# LM_HTR_001.net
KiCad netlist of a schematic drawn in Altium Designer
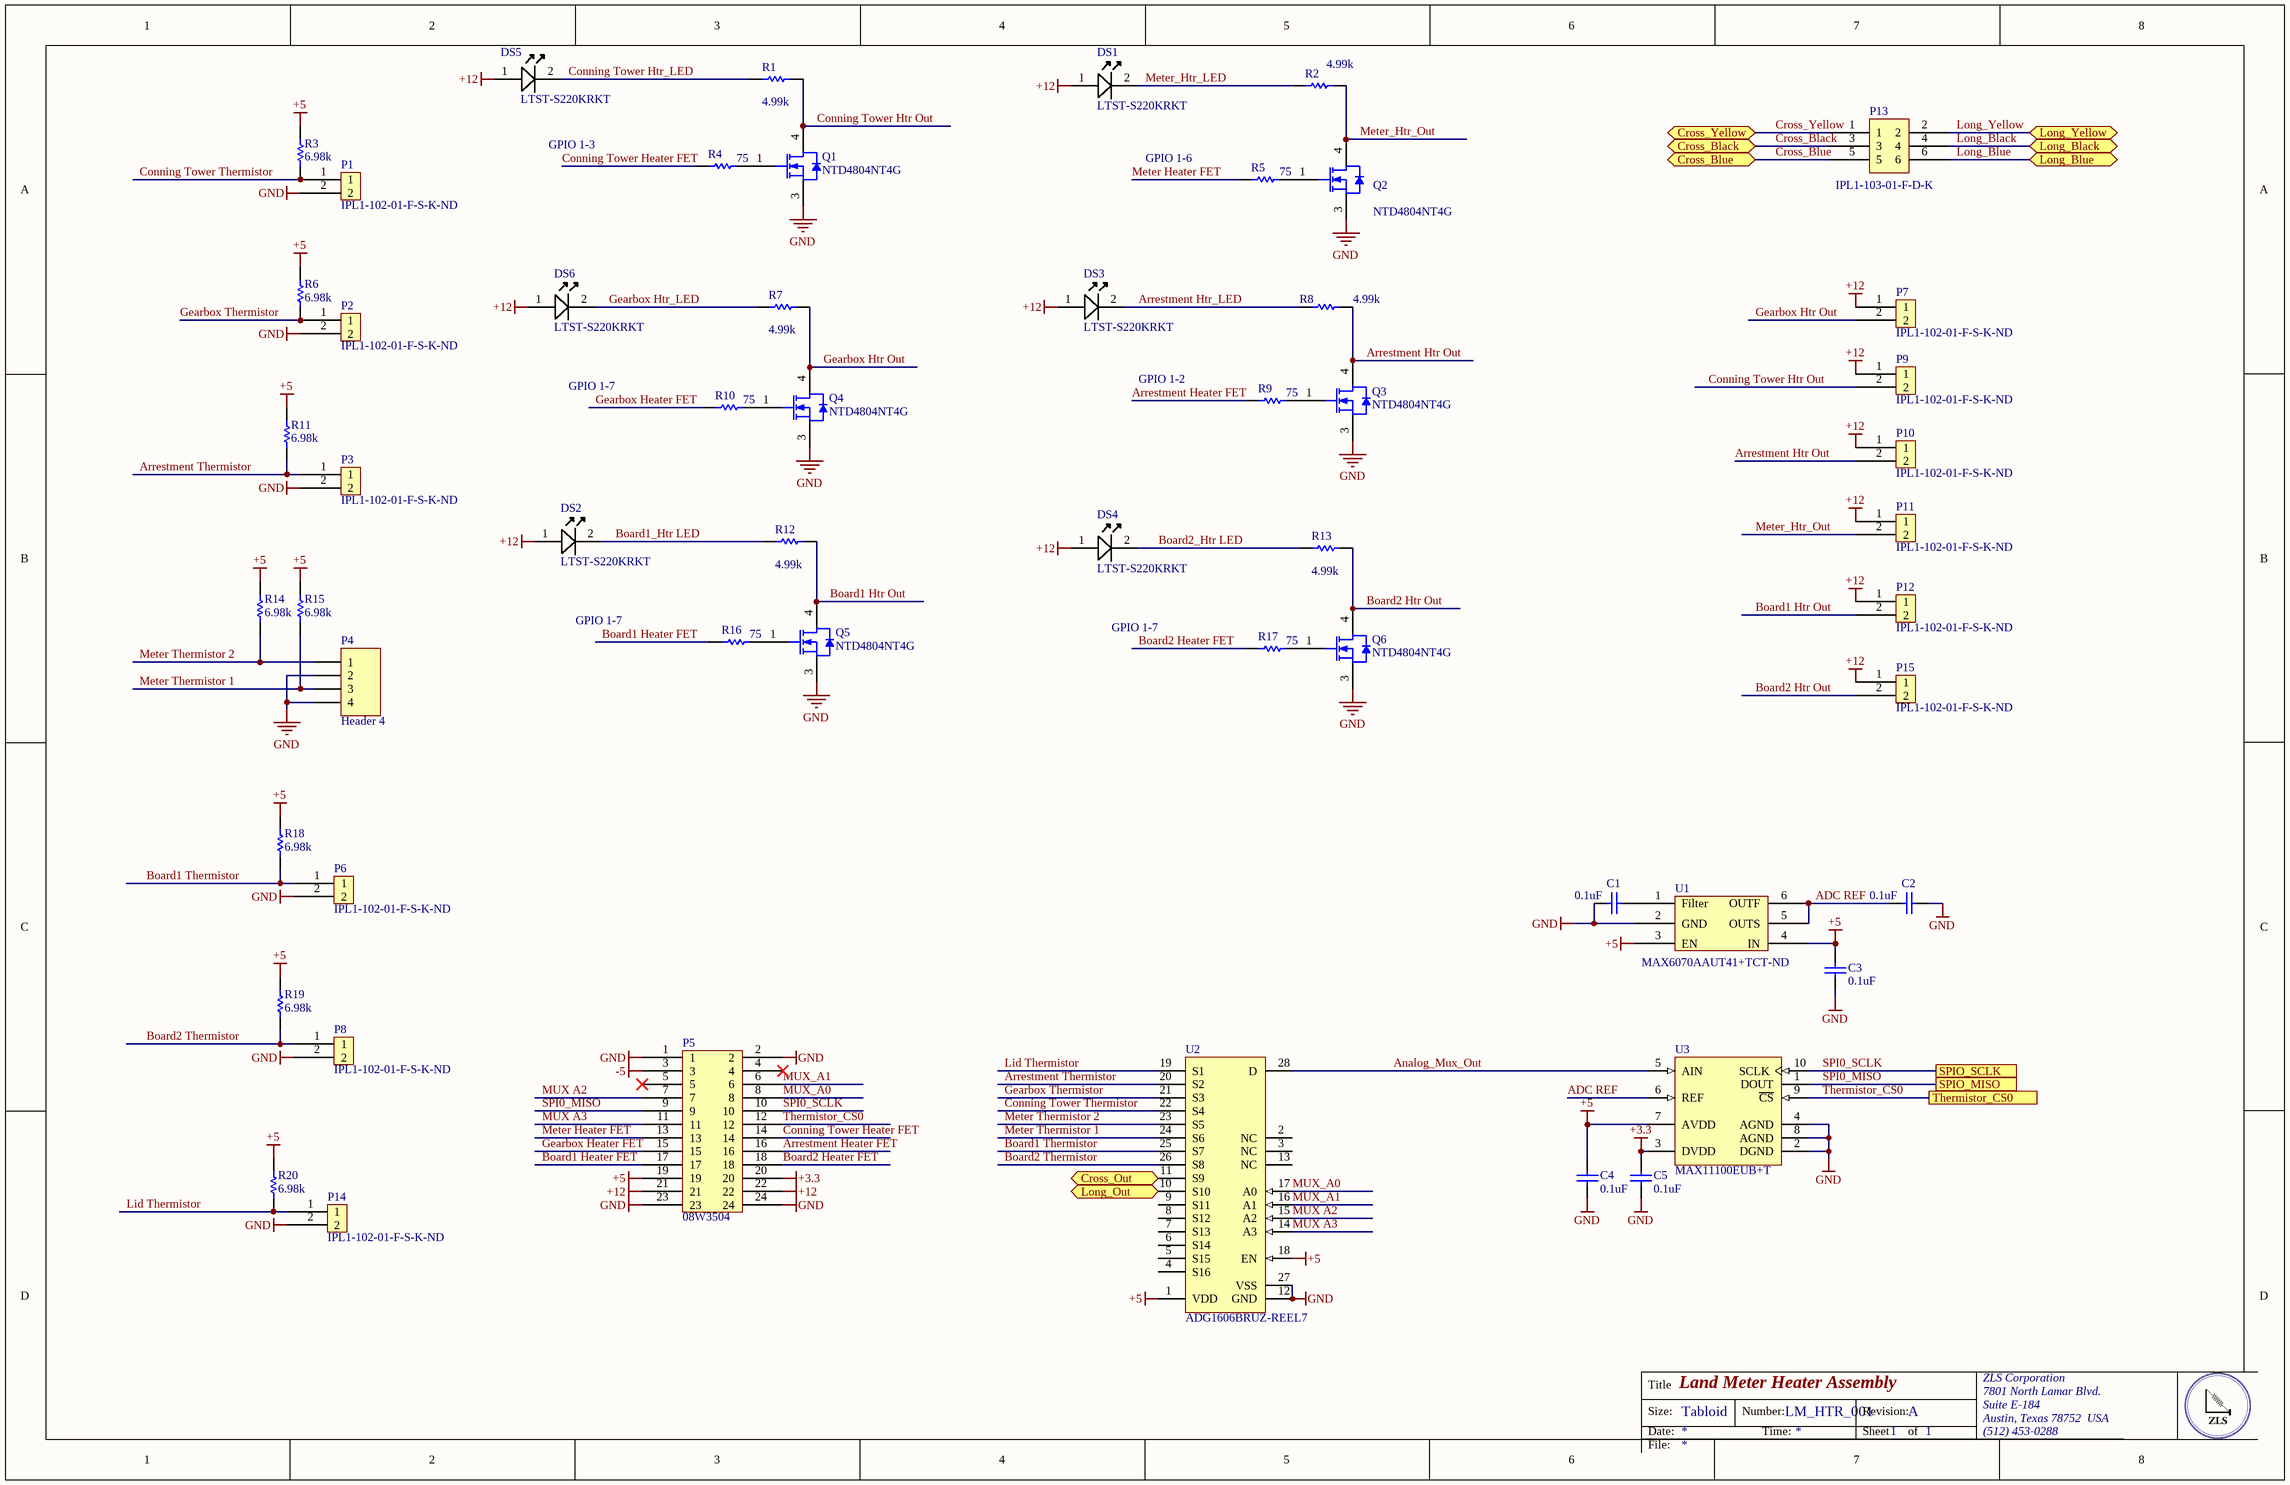
[diagram p0: LM_HTR_001.SchDoc]

(export (version "E")
  (design (tool "Eeschema 10.0.6"))
  (components
    (comp (ref "C1")
      (value "0.1uF")
      (footprint "CAPC0402(1005)60_L")
      (description "CAP CER 0.1UF 10V X7R 0402")
      (fields
        (field (name "MANUFACTURER") "Murata Electronics North America")
        (field (name "MANUFACTURER PART NUMBER") "GRM155R71A104KA01D")
      )
      (libsource (lib "Altium Content Vault") (part "CMP-1034-00252-1"))
    )
    (comp (ref "C2")
      (value "0.1uF")
      (footprint "CAPC0402(1005)60_L")
      (description "CAP CER 0.1UF 10V X7R 0402")
      (fields
        (field (name "MANUFACTURER") "Murata Electronics North America")
        (field (name "MANUFACTURER PART NUMBER") "GRM155R71A104KA01D")
      )
      (libsource (lib "Altium Content Vault") (part "CMP-1034-00252-1"))
    )
    (comp (ref "C3")
      (value "0.1uF")
      (footprint "CAPC0402(1005)60_L")
      (description "CAP CER 0.1UF 10V X7R 0402")
      (fields
        (field (name "MANUFACTURER") "Murata Electronics North America")
        (field (name "MANUFACTURER PART NUMBER") "GRM155R71A104KA01D")
      )
      (libsource (lib "Altium Content Vault") (part "CMP-1034-00252-1"))
    )
    (comp (ref "C4")
      (value "0.1uF")
      (footprint "CAPC0402(1005)60_L")
      (description "CAP CER 0.1UF 10V X7R 0402")
      (fields
        (field (name "MANUFACTURER") "Murata Electronics North America")
        (field (name "MANUFACTURER PART NUMBER") "GRM155R71A104KA01D")
      )
      (libsource (lib "Altium Content Vault") (part "CMP-1034-00252-1"))
    )
    (comp (ref "C5")
      (value "0.1uF")
      (footprint "CAPC0402(1005)60_L")
      (description "CAP CER 0.1UF 10V X7R 0402")
      (fields
        (field (name "MANUFACTURER") "Murata Electronics North America")
        (field (name "MANUFACTURER PART NUMBER") "GRM155R71A104KA01D")
      )
      (libsource (lib "Altium Content Vault") (part "CMP-1034-00252-1"))
    )
    (comp (ref "DS1")
      (value "Visible Name Value Type    False Description Lite-On LTST-S220KRKT Red LED, 631 nm 2012 (0805) Side View, Rectangle Lens SMD package STRING")
      (footprint "0805C_L")
      (fields
        (field (name "MANUFACTURER") "Vishay / Lite-On")
        (field (name "MANUFACTURER PART NUMBER") "LTST-S220KRKT")
      )
      (libsource (lib "*") (part "LED A/K"))
    )
    (comp (ref "DS2")
      (value "Visible Name Value Type    False Description Lite-On LTST-S220KRKT Red LED, 631 nm 2012 (0805) Side View, Rectangle Lens SMD package STRING")
      (footprint "0805C_L")
      (fields
        (field (name "MANUFACTURER") "Vishay / Lite-On")
        (field (name "MANUFACTURER PART NUMBER") "LTST-S220KRKT")
      )
      (libsource (lib "*") (part "LED A/K"))
    )
    (comp (ref "DS3")
      (value "Visible Name Value Type    False Description Lite-On LTST-S220KRKT Red LED, 631 nm 2012 (0805) Side View, Rectangle Lens SMD package STRING")
      (footprint "0805C_L")
      (fields
        (field (name "MANUFACTURER") "Vishay / Lite-On")
        (field (name "MANUFACTURER PART NUMBER") "LTST-S220KRKT")
      )
      (libsource (lib "*") (part "LED A/K"))
    )
    (comp (ref "DS4")
      (value "Visible Name Value Type    False Description Lite-On LTST-S220KRKT Red LED, 631 nm 2012 (0805) Side View, Rectangle Lens SMD package STRING")
      (footprint "0805C_L")
      (fields
        (field (name "MANUFACTURER") "Vishay / Lite-On")
        (field (name "MANUFACTURER PART NUMBER") "LTST-S220KRKT")
      )
      (libsource (lib "*") (part "LED A/K"))
    )
    (comp (ref "DS5")
      (value "Visible Name Value Type    False Description Lite-On LTST-S220KRKT Red LED, 631 nm 2012 (0805) Side View, Rectangle Lens SMD package STRING")
      (footprint "0805C_L")
      (fields
        (field (name "MANUFACTURER") "Vishay / Lite-On")
        (field (name "MANUFACTURER PART NUMBER") "LTST-S220KRKT")
      )
      (libsource (lib "*") (part "LED A/K"))
    )
    (comp (ref "DS6")
      (value "Visible Name Value Type    False Description Lite-On LTST-S220KRKT Red LED, 631 nm 2012 (0805) Side View, Rectangle Lens SMD package STRING")
      (footprint "0805C_L")
      (fields
        (field (name "MANUFACTURER") "Vishay / Lite-On")
        (field (name "MANUFACTURER PART NUMBER") "LTST-S220KRKT")
      )
      (libsource (lib "*") (part "LED A/K"))
    )
    (comp (ref "P1")
      (value "IPL1-102-01-F-S-K")
      (footprint "IPL1-102-01-F-S-K")
      (description ".100 TERMINAL ASSEMBLY")
      (fields
        (field (name "SUPPLIER PART NUMBER 1") "IPL1-102-01-F-S-K-ND")
        (field (name "MANUFACTURER") "Samtec Inc.")
      )
      (libsource (lib "ZLS_Schematic_lib") (part "IPL1-102-01-F-S-K"))
    )
    (comp (ref "P2")
      (value "IPL1-102-01-F-S-K")
      (footprint "IPL1-102-01-F-S-K")
      (description ".100 TERMINAL ASSEMBLY")
      (fields
        (field (name "SUPPLIER PART NUMBER 1") "IPL1-102-01-F-S-K-ND")
        (field (name "MANUFACTURER") "Samtec Inc.")
      )
      (libsource (lib "ZLS_Schematic_lib") (part "IPL1-102-01-F-S-K"))
    )
    (comp (ref "P3")
      (value "IPL1-102-01-F-S-K")
      (footprint "IPL1-102-01-F-S-K")
      (description ".100 TERMINAL ASSEMBLY")
      (fields
        (field (name "SUPPLIER PART NUMBER 1") "IPL1-102-01-F-S-K-ND")
        (field (name "MANUFACTURER") "Samtec Inc.")
      )
      (libsource (lib "ZLS_Schematic_lib") (part "IPL1-102-01-F-S-K"))
    )
    (comp (ref "P4")
      (value "Header 4")
      (footprint "IPL1-104-01-L-S-K")
      (description "Header, 4-Pin")
      (fields (field (name "PUBLISHER") "Altium Limited"))
      (libsource (lib "Miscellaneous Connectors") (part "Header 4"))
    )
    (comp (ref "P5")
      (value "IPL1-112-01-F-S-K")
      (footprint "IPL1-112-01-F-S-K")
      (description "IPL1-112-01-F-D-K")
      (fields (field (name "SUPPLIER PART NUMBER 1") "08W3504"))
      (libsource (lib "ZLS_Schematic_lib") (part "IPL1-112-01-F-S-K"))
    )
    (comp (ref "P6")
      (value "IPL1-102-01-F-S-K")
      (footprint "IPL1-102-01-F-S-K")
      (description ".100 TERMINAL ASSEMBLY")
      (fields
        (field (name "SUPPLIER PART NUMBER 1") "IPL1-102-01-F-S-K-ND")
        (field (name "MANUFACTURER") "Samtec Inc.")
      )
      (libsource (lib "ZLS_Schematic_lib") (part "IPL1-102-01-F-S-K"))
    )
    (comp (ref "P7")
      (value "IPL1-102-01-F-S-K")
      (footprint "IPL1-102-01-F-S-K")
      (description ".100 TERMINAL ASSEMBLY")
      (fields
        (field (name "SUPPLIER PART NUMBER 1") "IPL1-102-01-F-S-K-ND")
        (field (name "MANUFACTURER") "Samtec Inc.")
      )
      (libsource (lib "ZLS_Schematic_lib") (part "IPL1-102-01-F-S-K"))
    )
    (comp (ref "P8")
      (value "IPL1-102-01-F-S-K")
      (footprint "IPL1-102-01-F-S-K")
      (description ".100 TERMINAL ASSEMBLY")
      (fields
        (field (name "SUPPLIER PART NUMBER 1") "IPL1-102-01-F-S-K-ND")
        (field (name "MANUFACTURER") "Samtec Inc.")
      )
      (libsource (lib "ZLS_Schematic_lib") (part "IPL1-102-01-F-S-K"))
    )
    (comp (ref "P9")
      (value "IPL1-102-01-F-S-K")
      (footprint "IPL1-102-01-F-S-K")
      (description ".100 TERMINAL ASSEMBLY")
      (fields
        (field (name "SUPPLIER PART NUMBER 1") "IPL1-102-01-F-S-K-ND")
        (field (name "MANUFACTURER") "Samtec Inc.")
      )
      (libsource (lib "ZLS_Schematic_lib") (part "IPL1-102-01-F-S-K"))
    )
    (comp (ref "P10")
      (value "IPL1-102-01-F-S-K")
      (footprint "IPL1-102-01-F-S-K")
      (description ".100 TERMINAL ASSEMBLY")
      (fields
        (field (name "SUPPLIER PART NUMBER 1") "IPL1-102-01-F-S-K-ND")
        (field (name "MANUFACTURER") "Samtec Inc.")
      )
      (libsource (lib "ZLS_Schematic_lib") (part "IPL1-102-01-F-S-K"))
    )
    (comp (ref "P11")
      (value "IPL1-102-01-F-S-K")
      (footprint "IPL1-102-01-F-S-K")
      (description ".100 TERMINAL ASSEMBLY")
      (fields
        (field (name "SUPPLIER PART NUMBER 1") "IPL1-102-01-F-S-K-ND")
        (field (name "MANUFACTURER") "Samtec Inc.")
      )
      (libsource (lib "ZLS_Schematic_lib") (part "IPL1-102-01-F-S-K"))
    )
    (comp (ref "P12")
      (value "IPL1-102-01-F-S-K")
      (footprint "IPL1-102-01-F-S-K")
      (description ".100 TERMINAL ASSEMBLY")
      (fields
        (field (name "SUPPLIER PART NUMBER 1") "IPL1-102-01-F-S-K-ND")
        (field (name "MANUFACTURER") "Samtec Inc.")
      )
      (libsource (lib "ZLS_Schematic_lib") (part "IPL1-102-01-F-S-K"))
    )
    (comp (ref "P13")
      (value "IPL1-103-01-F-D")
      (footprint "IPL1-103-01-F-D")
      (fields
        (field (name "MANUFACTURER") "SAMTEC")
        (field (name "MANUFACTURER PART NUMBER") "IPL1-103-01-F-D-K")
        (field (name "COMPONENTLINK1URL") "https://webassistants.partcommunity.com/23d-libs/samtec/search/resolve.html?EMAIL=mysamtec@samtec.com&PN=HTSW-114-05-F-D")
        (field (name "COMPONENTLINK1DESCRIPTION") "https://webassistants.partcommunity.com/23d-libs/samtec/search/resolve.html?EMAIL=mysamtec@samtec.com&PN=HTSW-114-05-F-D")
      )
      (libsource (lib "ZLS_Schematic_lib") (part "IPL1-103-01-F-D"))
    )
    (comp (ref "P14")
      (value "IPL1-102-01-F-S-K")
      (footprint "IPL1-102-01-F-S-K")
      (description ".100 TERMINAL ASSEMBLY")
      (fields
        (field (name "SUPPLIER PART NUMBER 1") "IPL1-102-01-F-S-K-ND")
        (field (name "MANUFACTURER") "Samtec Inc.")
      )
      (libsource (lib "ZLS_Schematic_lib") (part "IPL1-102-01-F-S-K"))
    )
    (comp (ref "P15")
      (value "IPL1-102-01-F-S-K")
      (footprint "IPL1-102-01-F-S-K")
      (description ".100 TERMINAL ASSEMBLY")
      (fields
        (field (name "SUPPLIER PART NUMBER 1") "IPL1-102-01-F-S-K-ND")
        (field (name "MANUFACTURER") "Samtec Inc.")
      )
      (libsource (lib "ZLS_Schematic_lib") (part "IPL1-102-01-F-S-K"))
    )
    (comp (ref "Q1")
      (value "NTD4804NT4G")
      (footprint "ONSC-DPAK-3-369AA-01_V")
      (description "Power MOSFET, 30 V, 117 A, Single N-Channel, 3-Pin DPAK, Pb-Free, Tape and Reel")
      (fields (field (name "MANUFACTURER") "On Semiconductor"))
      (libsource (lib "Altium Content Vault") (part "CMP-1058-00341-1"))
    )
    (comp (ref "Q2")
      (value "NTD4804NT4G")
      (footprint "ONSC-DPAK-3-369AA-01_V")
      (description "Power MOSFET, 30 V, 117 A, Single N-Channel, 3-Pin DPAK, Pb-Free, Tape and Reel")
      (fields (field (name "MANUFACTURER") "On Semiconductor"))
      (libsource (lib "Altium Content Vault") (part "CMP-1058-00341-1"))
    )
    (comp (ref "Q3")
      (value "NTD4804NT4G")
      (footprint "ONSC-DPAK-3-369AA-01_V")
      (description "Power MOSFET, 30 V, 117 A, Single N-Channel, 3-Pin DPAK, Pb-Free, Tape and Reel")
      (fields (field (name "MANUFACTURER") "On Semiconductor"))
      (libsource (lib "Altium Content Vault") (part "CMP-1058-00341-1"))
    )
    (comp (ref "Q4")
      (value "NTD4804NT4G")
      (footprint "ONSC-DPAK-3-369AA-01_V")
      (description "Power MOSFET, 30 V, 117 A, Single N-Channel, 3-Pin DPAK, Pb-Free, Tape and Reel")
      (fields (field (name "MANUFACTURER") "On Semiconductor"))
      (libsource (lib "Altium Content Vault") (part "CMP-1058-00341-1"))
    )
    (comp (ref "Q5")
      (value "NTD4804NT4G")
      (footprint "ONSC-DPAK-3-369AA-01_V")
      (description "Power MOSFET, 30 V, 117 A, Single N-Channel, 3-Pin DPAK, Pb-Free, Tape and Reel")
      (fields (field (name "MANUFACTURER") "On Semiconductor"))
      (libsource (lib "Altium Content Vault") (part "CMP-1058-00341-1"))
    )
    (comp (ref "Q6")
      (value "NTD4804NT4G")
      (footprint "ONSC-DPAK-3-369AA-01_V")
      (description "Power MOSFET, 30 V, 117 A, Single N-Channel, 3-Pin DPAK, Pb-Free, Tape and Reel")
      (fields (field (name "MANUFACTURER") "On Semiconductor"))
      (libsource (lib "Altium Content Vault") (part "CMP-1058-00341-1"))
    )
    (comp (ref "R1")
      (value "~")
      (footprint "RESC0805(2012)_L")
      (fields
        (field (name "MANUFACTURER") "Vishay Dale")
        (field (name "MANUFACTURER PART NUMBER") "CRCW08054K99FKEA")
        (field (name "RESISTANCE (OHMS)") "4.99k")
        (field (name "TOLERANCE") "±1%")
      )
      (libsource (lib "Altium Content Vault") (part "CMP-1013-00393-1"))
    )
    (comp (ref "R2")
      (value "~")
      (footprint "RESC0805(2012)_L")
      (fields
        (field (name "MANUFACTURER") "Vishay Dale")
        (field (name "MANUFACTURER PART NUMBER") "CRCW08054K99FKEA")
        (field (name "RESISTANCE (OHMS)") "4.99k")
        (field (name "TOLERANCE") "±1%")
      )
      (libsource (lib "Altium Content Vault") (part "CMP-1013-00393-1"))
    )
    (comp (ref "R3")
      (value "6K98 1% 0805(2012)")
      (footprint "RESC0805(2012)_N")
      (description "6K98 0.125W 1% 0805 (2012 Metric)  SMD")
      (fields
        (field (name "MANUFACTURER") "Vishay Dale")
        (field (name "MANUFACTURER PART NUMBER") "CRCW08056K98FKEA")
        (field (name "RESISTANCE (OHMS)") "6.98k")
      )
      (libsource (lib "Altium Content Vault") (part "CMP-1013-00606-1"))
    )
    (comp (ref "R4")
      (value "~")
      (footprint "RESC0805(2012)_L")
      (fields
        (field (name "MANUFACTURER") "Vishay Dale")
        (field (name "MANUFACTURER PART NUMBER") "CRCW080575R0FKEA")
        (field (name "RESISTANCE (OHMS)") "75")
        (field (name "TOLERANCE") "±1%")
      )
      (libsource (lib "Altium Content Vault") (part "CMP-1013-00393-1"))
    )
    (comp (ref "R5")
      (value "~")
      (footprint "RESC0805(2012)_L")
      (fields
        (field (name "MANUFACTURER") "Vishay Dale")
        (field (name "MANUFACTURER PART NUMBER") "CRCW080575R0FKEA")
        (field (name "RESISTANCE (OHMS)") "75")
        (field (name "TOLERANCE") "±1%")
      )
      (libsource (lib "Altium Content Vault") (part "CMP-1013-00393-1"))
    )
    (comp (ref "R6")
      (value "6K98 1% 0805(2012)")
      (footprint "RESC0805(2012)_N")
      (description "6K98 0.125W 1% 0805 (2012 Metric)  SMD")
      (fields
        (field (name "MANUFACTURER") "Vishay Dale")
        (field (name "MANUFACTURER PART NUMBER") "CRCW08056K98FKEA")
        (field (name "RESISTANCE (OHMS)") "6.98k")
      )
      (libsource (lib "Altium Content Vault") (part "CMP-1013-00606-1"))
    )
    (comp (ref "R7")
      (value "~")
      (footprint "RESC0805(2012)_L")
      (fields
        (field (name "MANUFACTURER") "Vishay Dale")
        (field (name "MANUFACTURER PART NUMBER") "CRCW08054K99FKEA")
        (field (name "RESISTANCE (OHMS)") "4.99k")
        (field (name "TOLERANCE") "±1%")
      )
      (libsource (lib "Altium Content Vault") (part "CMP-1013-00393-1"))
    )
    (comp (ref "R8")
      (value "~")
      (footprint "RESC0805(2012)_L")
      (fields
        (field (name "MANUFACTURER") "Vishay Dale")
        (field (name "MANUFACTURER PART NUMBER") "CRCW08054K99FKEA")
        (field (name "RESISTANCE (OHMS)") "4.99k")
        (field (name "TOLERANCE") "±1%")
      )
      (libsource (lib "Altium Content Vault") (part "CMP-1013-00393-1"))
    )
    (comp (ref "R9")
      (value "~")
      (footprint "RESC0805(2012)_L")
      (fields
        (field (name "MANUFACTURER") "Vishay Dale")
        (field (name "MANUFACTURER PART NUMBER") "CRCW080575R0FKEA")
        (field (name "RESISTANCE (OHMS)") "75")
        (field (name "TOLERANCE") "±1%")
      )
      (libsource (lib "Altium Content Vault") (part "CMP-1013-00393-1"))
    )
    (comp (ref "R10")
      (value "~")
      (footprint "RESC0805(2012)_L")
      (fields
        (field (name "MANUFACTURER") "Vishay Dale")
        (field (name "MANUFACTURER PART NUMBER") "CRCW080575R0FKEA")
        (field (name "RESISTANCE (OHMS)") "75")
        (field (name "TOLERANCE") "±1%")
      )
      (libsource (lib "Altium Content Vault") (part "CMP-1013-00393-1"))
    )
    (comp (ref "R11")
      (value "6K98 1% 0805(2012)")
      (footprint "RESC0805(2012)_N")
      (description "6K98 0.125W 1% 0805 (2012 Metric)  SMD")
      (fields
        (field (name "MANUFACTURER") "Vishay Dale")
        (field (name "MANUFACTURER PART NUMBER") "CRCW08056K98FKEA")
        (field (name "RESISTANCE (OHMS)") "6.98k")
      )
      (libsource (lib "Altium Content Vault") (part "CMP-1013-00606-1"))
    )
    (comp (ref "R12")
      (value "~")
      (footprint "RESC0805(2012)_L")
      (fields
        (field (name "MANUFACTURER") "Vishay Dale")
        (field (name "MANUFACTURER PART NUMBER") "CRCW08054K99FKEA")
        (field (name "RESISTANCE (OHMS)") "4.99k")
        (field (name "TOLERANCE") "±1%")
      )
      (libsource (lib "Altium Content Vault") (part "CMP-1013-00393-1"))
    )
    (comp (ref "R13")
      (value "~")
      (footprint "RESC0805(2012)_L")
      (fields
        (field (name "MANUFACTURER") "Vishay Dale")
        (field (name "MANUFACTURER PART NUMBER") "CRCW08054K99FKEA")
        (field (name "RESISTANCE (OHMS)") "4.99k")
        (field (name "TOLERANCE") "±1%")
      )
      (libsource (lib "Altium Content Vault") (part "CMP-1013-00393-1"))
    )
    (comp (ref "R14")
      (value "6K98 1% 0805(2012)")
      (footprint "RESC0805(2012)_N")
      (description "6K98 0.125W 1% 0805 (2012 Metric)  SMD")
      (fields
        (field (name "MANUFACTURER") "Vishay Dale")
        (field (name "MANUFACTURER PART NUMBER") "CRCW08056K98FKEA")
        (field (name "RESISTANCE (OHMS)") "6.98k")
      )
      (libsource (lib "Altium Content Vault") (part "CMP-1013-00606-1"))
    )
    (comp (ref "R15")
      (value "6K98 1% 0805(2012)")
      (footprint "RESC0805(2012)_N")
      (description "6K98 0.125W 1% 0805 (2012 Metric)  SMD")
      (fields
        (field (name "MANUFACTURER") "Vishay Dale")
        (field (name "MANUFACTURER PART NUMBER") "CRCW08056K98FKEA")
        (field (name "RESISTANCE (OHMS)") "6.98k")
      )
      (libsource (lib "Altium Content Vault") (part "CMP-1013-00606-1"))
    )
    (comp (ref "R16")
      (value "~")
      (footprint "RESC0805(2012)_L")
      (fields
        (field (name "MANUFACTURER") "Vishay Dale")
        (field (name "MANUFACTURER PART NUMBER") "CRCW080575R0FKEA")
        (field (name "RESISTANCE (OHMS)") "75")
        (field (name "TOLERANCE") "±1%")
      )
      (libsource (lib "Altium Content Vault") (part "CMP-1013-00393-1"))
    )
    (comp (ref "R17")
      (value "~")
      (footprint "RESC0805(2012)_L")
      (fields
        (field (name "MANUFACTURER") "Vishay Dale")
        (field (name "MANUFACTURER PART NUMBER") "CRCW080575R0FKEA")
        (field (name "RESISTANCE (OHMS)") "75")
        (field (name "TOLERANCE") "±1%")
      )
      (libsource (lib "Altium Content Vault") (part "CMP-1013-00393-1"))
    )
    (comp (ref "R18")
      (value "6K98 1% 0805(2012)")
      (footprint "RESC0805(2012)_N")
      (description "6K98 0.125W 1% 0805 (2012 Metric)  SMD")
      (fields
        (field (name "MANUFACTURER") "Vishay Dale")
        (field (name "MANUFACTURER PART NUMBER") "CRCW08056K98FKEA")
        (field (name "RESISTANCE (OHMS)") "6.98k")
      )
      (libsource (lib "Altium Content Vault") (part "CMP-1013-00606-1"))
    )
    (comp (ref "R19")
      (value "6K98 1% 0805(2012)")
      (footprint "RESC0805(2012)_N")
      (description "6K98 0.125W 1% 0805 (2012 Metric)  SMD")
      (fields
        (field (name "MANUFACTURER") "Vishay Dale")
        (field (name "MANUFACTURER PART NUMBER") "CRCW08056K98FKEA")
        (field (name "RESISTANCE (OHMS)") "6.98k")
      )
      (libsource (lib "Altium Content Vault") (part "CMP-1013-00606-1"))
    )
    (comp (ref "R20")
      (value "6K98 1% 0805(2012)")
      (footprint "RESC0805(2012)_N")
      (description "6K98 0.125W 1% 0805 (2012 Metric)  SMD")
      (fields
        (field (name "MANUFACTURER") "Vishay Dale")
        (field (name "MANUFACTURER PART NUMBER") "CRCW08056K98FKEA")
        (field (name "RESISTANCE (OHMS)") "6.98k")
      )
      (libsource (lib "Altium Content Vault") (part "CMP-1013-00606-1"))
    )
    (comp (ref "U1")
      (value "MAX6070AAUT41+T")
      (footprint "SOT95P280X445-6N")
      (description "IC VREF SERIES 4.096V SOT23")
      (fields
        (field (name "SUPPLIER PART NUMBER 1") "MAX6070AAUT41+TCT-ND")
        (field (name "MANUFACTURER") "Maxim Integrated")
        (field (name "TOLERANCE") "±0.04%")
      )
      (libsource (lib "ZLS_Schematic_lib") (part "MAX6070AAUT41+T"))
    )
    (comp (ref "U2")
      (value "ADG1606BRUZ-REEL7")
      (footprint "ADI-RU-28_M")
      (description "4.5 Ohm Ron, 16-Channel, +/-5 V,+12 V,+5 V and +3.3 V Multiplexer, 28-pin SOP (RU-28), Reel")
      (fields (field (name "MANUFACTURER") "Analog Devices"))
      (libsource (lib "Altium Content Vault") (part "ADI-ADG1606-RU-28"))
    )
    (comp (ref "U3")
      (value "MAX11100EUB+T")
      (footprint "U10+2_L")
      (description "16-Bit, +5V, 200ksps ADC with 10uA Shutdown, 10-Pin uMAX, -40°C to +85°C, Pb-Free, Tape and Reel")
      (libsource (lib "Altium Content Vault") (part "CON-ADC-MAX11100-IL10"))
    )
  )
  (nets
    (net (code "1") (name "+3.3") (class "Default")
      (node (ref "C5") (pin "1") (pinfunction "1_1") (pintype "passive"))
      (node (ref "P5") (pin "20") (pinfunction "20_20") (pintype "passive"))
      (node (ref "U3") (pin "3") (pinfunction "DVDD_3") (pintype "power_in"))
    )
    (net (code "2") (name "+5") (class "Default")
      (node (ref "C3") (pin "1") (pinfunction "1_1") (pintype "passive"))
      (node (ref "C4") (pin "1") (pinfunction "1_1") (pintype "passive"))
      (node (ref "P5") (pin "19") (pinfunction "19_19") (pintype "passive"))
      (node (ref "R11") (pin "1") (pinfunction "1_1") (pintype "passive"))
      (node (ref "R14") (pin "1") (pinfunction "1_1") (pintype "passive"))
      (node (ref "R15") (pin "2") (pinfunction "2_2") (pintype "passive"))
      (node (ref "R18") (pin "1") (pinfunction "1_1") (pintype "passive"))
      (node (ref "R19") (pin "1") (pinfunction "1_1") (pintype "passive"))
      (node (ref "R20") (pin "1") (pinfunction "1_1") (pintype "passive"))
      (node (ref "R3") (pin "2") (pinfunction "2_2") (pintype "passive"))
      (node (ref "R6") (pin "2") (pinfunction "2_2") (pintype "passive"))
      (node (ref "U1") (pin "3") (pinfunction "EN_3") (pintype "passive"))
      (node (ref "U1") (pin "4") (pinfunction "IN_4") (pintype "passive"))
      (node (ref "U2") (pin "1") (pinfunction "VDD_1") (pintype "power_in"))
      (node (ref "U2") (pin "18") (pinfunction "EN_18") (pintype "input"))
      (node (ref "U3") (pin "7") (pinfunction "AVDD_7") (pintype "power_in"))
    )
    (net (code "3") (name "+12") (class "Default")
      (node (ref "DS1") (pin "1") (pinfunction "A_1") (pintype "passive"))
      (node (ref "DS2") (pin "1") (pinfunction "A_1") (pintype "passive"))
      (node (ref "DS3") (pin "1") (pinfunction "A_1") (pintype "passive"))
      (node (ref "DS4") (pin "1") (pinfunction "A_1") (pintype "passive"))
      (node (ref "DS5") (pin "1") (pinfunction "A_1") (pintype "passive"))
      (node (ref "DS6") (pin "1") (pinfunction "A_1") (pintype "passive"))
      (node (ref "P10") (pin "1") (pinfunction "1_1") (pintype "passive"))
      (node (ref "P11") (pin "1") (pinfunction "1_1") (pintype "passive"))
      (node (ref "P12") (pin "1") (pinfunction "1_1") (pintype "passive"))
      (node (ref "P15") (pin "1") (pinfunction "1_1") (pintype "passive"))
      (node (ref "P5") (pin "21") (pinfunction "21_21") (pintype "passive"))
      (node (ref "P5") (pin "22") (pinfunction "22_22") (pintype "passive"))
      (node (ref "P7") (pin "1") (pinfunction "1_1") (pintype "passive"))
      (node (ref "P9") (pin "1") (pinfunction "1_1") (pintype "passive"))
    )
    (net (code "4") (name "-5") (class "Default")
      (node (ref "P5") (pin "3") (pinfunction "3_3") (pintype "passive"))
    )
    (net (code "5") (name "/ADC REF") (class "Default")
      (node (ref "C2") (pin "2") (pinfunction "2_2") (pintype "passive"))
      (node (ref "U1") (pin "5") (pinfunction "OUTS_5") (pintype "passive"))
      (node (ref "U1") (pin "6") (pinfunction "OUTF_6") (pintype "passive"))
      (node (ref "U3") (pin "6") (pinfunction "REF_6") (pintype "input"))
    )
    (net (code "6") (name "/Analog_Mux_Out") (class "Default")
      (node (ref "U2") (pin "28") (pinfunction "D_28") (pintype "passive"))
      (node (ref "U3") (pin "5") (pinfunction "AIN_5") (pintype "input"))
    )
    (net (code "7") (name "/Arrestment Heater FET") (class "Default")
      (node (ref "P5") (pin "16") (pinfunction "16_16") (pintype "passive"))
      (node (ref "R9") (pin "1") (pinfunction "1_1") (pintype "passive"))
    )
    (net (code "8") (name "/Arrestment Htr Out") (class "Default")
      (node (ref "P10") (pin "2") (pinfunction "2_2") (pintype "passive"))
      (node (ref "Q3") (pin "4") (pinfunction "D_4") (pintype "passive"))
      (node (ref "R8") (pin "2") (pinfunction "2_2") (pintype "passive"))
    )
    (net (code "9") (name "/Arrestment Htr_LED") (class "Default")
      (node (ref "DS3") (pin "2") (pinfunction "K_2") (pintype "passive"))
      (node (ref "R8") (pin "1") (pinfunction "1_1") (pintype "passive"))
    )
    (net (code "10") (name "/Arrestment Thermistor") (class "Default")
      (node (ref "P3") (pin "1") (pinfunction "1_1") (pintype "passive"))
      (node (ref "R11") (pin "2") (pinfunction "2_2") (pintype "passive"))
      (node (ref "U2") (pin "20") (pinfunction "S2_20") (pintype "passive"))
    )
    (net (code "11") (name "/Board1 Heater FET") (class "Default")
      (node (ref "P5") (pin "17") (pinfunction "17_17") (pintype "passive"))
      (node (ref "R16") (pin "1") (pinfunction "1_1") (pintype "passive"))
    )
    (net (code "12") (name "/Board1 Htr Out") (class "Default")
      (node (ref "P12") (pin "2") (pinfunction "2_2") (pintype "passive"))
      (node (ref "Q5") (pin "4") (pinfunction "D_4") (pintype "passive"))
      (node (ref "R12") (pin "1") (pinfunction "1_1") (pintype "passive"))
    )
    (net (code "13") (name "/Board1 Thermistor") (class "Default")
      (node (ref "P6") (pin "1") (pinfunction "1_1") (pintype "passive"))
      (node (ref "R18") (pin "2") (pinfunction "2_2") (pintype "passive"))
      (node (ref "U2") (pin "25") (pinfunction "S7_25") (pintype "passive"))
    )
    (net (code "14") (name "/Board1_Htr LED") (class "Default")
      (node (ref "DS2") (pin "2") (pinfunction "K_2") (pintype "passive"))
      (node (ref "R12") (pin "2") (pinfunction "2_2") (pintype "passive"))
    )
    (net (code "15") (name "/Board2 Heater FET") (class "Default")
      (node (ref "P5") (pin "18") (pinfunction "18_18") (pintype "passive"))
      (node (ref "R17") (pin "1") (pinfunction "1_1") (pintype "passive"))
    )
    (net (code "16") (name "/Board2 Htr Out") (class "Default")
      (node (ref "P15") (pin "2") (pinfunction "2_2") (pintype "passive"))
      (node (ref "Q6") (pin "4") (pinfunction "D_4") (pintype "passive"))
      (node (ref "R13") (pin "1") (pinfunction "1_1") (pintype "passive"))
    )
    (net (code "17") (name "/Board2 Thermistor") (class "Default")
      (node (ref "P8") (pin "1") (pinfunction "1_1") (pintype "passive"))
      (node (ref "R19") (pin "2") (pinfunction "2_2") (pintype "passive"))
      (node (ref "U2") (pin "26") (pinfunction "S8_26") (pintype "passive"))
    )
    (net (code "18") (name "/Board2_Htr LED") (class "Default")
      (node (ref "DS4") (pin "2") (pinfunction "K_2") (pintype "passive"))
      (node (ref "R13") (pin "2") (pinfunction "2_2") (pintype "passive"))
    )
    (net (code "19") (name "/Conning Tower Heater FET") (class "Default")
      (node (ref "P5") (pin "14") (pinfunction "14_14") (pintype "passive"))
      (node (ref "R4") (pin "1") (pinfunction "1_1") (pintype "passive"))
    )
    (net (code "20") (name "/Conning Tower Htr Out") (class "Default")
      (node (ref "P9") (pin "2") (pinfunction "2_2") (pintype "passive"))
      (node (ref "Q1") (pin "4") (pinfunction "D_4") (pintype "passive"))
      (node (ref "R1") (pin "1") (pinfunction "1_1") (pintype "passive"))
    )
    (net (code "21") (name "/Conning Tower Htr_LED") (class "Default")
      (node (ref "DS5") (pin "2") (pinfunction "K_2") (pintype "passive"))
      (node (ref "R1") (pin "2") (pinfunction "2_2") (pintype "passive"))
    )
    (net (code "22") (name "/Conning Tower Thermistor") (class "Default")
      (node (ref "P1") (pin "1") (pinfunction "1_1") (pintype "passive"))
      (node (ref "R3") (pin "1") (pinfunction "1_1") (pintype "passive"))
      (node (ref "U2") (pin "22") (pinfunction "S4_22") (pintype "passive"))
    )
    (net (code "23") (name "/Cross_Black") (class "Default")
      (node (ref "P13") (pin "3") (pinfunction "3_3") (pintype "passive"))
    )
    (net (code "24") (name "/Cross_Blue") (class "Default")
      (node (ref "P13") (pin "5") (pinfunction "5_5") (pintype "passive"))
    )
    (net (code "25") (name "/Cross_Out") (class "Default")
      (node (ref "U2") (pin "11") (pinfunction "S9_11") (pintype "passive"))
    )
    (net (code "26") (name "/Cross_Yellow") (class "Default")
      (node (ref "P13") (pin "1") (pinfunction "1_1") (pintype "passive"))
    )
    (net (code "27") (name "/Gearbox Heater FET") (class "Default")
      (node (ref "P5") (pin "15") (pinfunction "15_15") (pintype "passive"))
      (node (ref "R10") (pin "1") (pinfunction "1_1") (pintype "passive"))
    )
    (net (code "28") (name "/Gearbox Htr Out") (class "Default")
      (node (ref "P7") (pin "2") (pinfunction "2_2") (pintype "passive"))
      (node (ref "Q4") (pin "4") (pinfunction "D_4") (pintype "passive"))
      (node (ref "R7") (pin "1") (pinfunction "1_1") (pintype "passive"))
    )
    (net (code "29") (name "/Gearbox Htr_LED") (class "Default")
      (node (ref "DS6") (pin "2") (pinfunction "K_2") (pintype "passive"))
      (node (ref "R7") (pin "2") (pinfunction "2_2") (pintype "passive"))
    )
    (net (code "30") (name "/Gearbox Thermistor") (class "Default")
      (node (ref "P2") (pin "1") (pinfunction "1_1") (pintype "passive"))
      (node (ref "R6") (pin "1") (pinfunction "1_1") (pintype "passive"))
      (node (ref "U2") (pin "21") (pinfunction "S3_21") (pintype "passive"))
    )
    (net (code "31") (name "/Lid Thermistor") (class "Default")
      (node (ref "P14") (pin "1") (pinfunction "1_1") (pintype "passive"))
      (node (ref "R20") (pin "2") (pinfunction "2_2") (pintype "passive"))
      (node (ref "U2") (pin "19") (pinfunction "S1_19") (pintype "passive"))
    )
    (net (code "32") (name "/Long_Black") (class "Default")
      (node (ref "P13") (pin "4") (pinfunction "4_4") (pintype "passive"))
    )
    (net (code "33") (name "/Long_Blue") (class "Default")
      (node (ref "P13") (pin "6") (pinfunction "6_6") (pintype "passive"))
    )
    (net (code "34") (name "/Long_Out") (class "Default")
      (node (ref "U2") (pin "10") (pinfunction "S10_10") (pintype "passive"))
    )
    (net (code "35") (name "/Long_Yellow") (class "Default")
      (node (ref "P13") (pin "2") (pinfunction "2_2") (pintype "passive"))
    )
    (net (code "36") (name "/MUX A2") (class "Default")
      (node (ref "P5") (pin "7") (pinfunction "7_7") (pintype "passive"))
      (node (ref "U2") (pin "15") (pinfunction "A2_15") (pintype "input"))
    )
    (net (code "37") (name "/MUX A3") (class "Default")
      (node (ref "P5") (pin "11") (pinfunction "11_11") (pintype "passive"))
      (node (ref "U2") (pin "14") (pinfunction "A3_14") (pintype "input"))
    )
    (net (code "38") (name "/MUX_A0") (class "Default")
      (node (ref "P5") (pin "8") (pinfunction "8_8") (pintype "passive"))
      (node (ref "U2") (pin "17") (pinfunction "A0_17") (pintype "input"))
    )
    (net (code "39") (name "/MUX_A1") (class "Default")
      (node (ref "P5") (pin "6") (pinfunction "6_6") (pintype "passive"))
      (node (ref "U2") (pin "16") (pinfunction "A1_16") (pintype "input"))
    )
    (net (code "40") (name "/Meter Heater FET") (class "Default")
      (node (ref "P5") (pin "13") (pinfunction "13_13") (pintype "passive"))
      (node (ref "R5") (pin "1") (pinfunction "1_1") (pintype "passive"))
    )
    (net (code "41") (name "/Meter Thermistor 1") (class "Default")
      (node (ref "P4") (pin "3") (pinfunction "3_3") (pintype "passive"))
      (node (ref "R15") (pin "1") (pinfunction "1_1") (pintype "passive"))
      (node (ref "U2") (pin "24") (pinfunction "S6_24") (pintype "passive"))
    )
    (net (code "42") (name "/Meter Thermistor 2") (class "Default")
      (node (ref "P4") (pin "1") (pinfunction "1_1") (pintype "passive"))
      (node (ref "R14") (pin "2") (pinfunction "2_2") (pintype "passive"))
      (node (ref "U2") (pin "23") (pinfunction "S5_23") (pintype "passive"))
    )
    (net (code "43") (name "/Meter_Htr_LED") (class "Default")
      (node (ref "DS1") (pin "2") (pinfunction "K_2") (pintype "passive"))
      (node (ref "R2") (pin "1") (pinfunction "1_1") (pintype "passive"))
    )
    (net (code "44") (name "/Meter_Htr_Out") (class "Default")
      (node (ref "P11") (pin "2") (pinfunction "2_2") (pintype "passive"))
      (node (ref "Q2") (pin "4") (pinfunction "D_4") (pintype "passive"))
      (node (ref "R2") (pin "2") (pinfunction "2_2") (pintype "passive"))
    )
    (net (code "45") (name "/SPI0_MISO") (class "Default")
      (node (ref "P5") (pin "9") (pinfunction "9_9") (pintype "passive"))
      (node (ref "U3") (pin "1") (pinfunction "DOUT_1") (pintype "tri_state"))
    )
    (net (code "46") (name "/SPI0_SCLK") (class "Default")
      (node (ref "P5") (pin "10") (pinfunction "10_10") (pintype "passive"))
      (node (ref "U3") (pin "10") (pinfunction "SCLK_10") (pintype "input"))
    )
    (net (code "47") (name "/Thermistor_CS0") (class "Default")
      (node (ref "P5") (pin "12") (pinfunction "12_12") (pintype "passive"))
      (node (ref "U3") (pin "9") (pinfunction "~{CS}_9") (pintype "input"))
    )
    (net (code "48") (name "GND") (class "Default")
      (node (ref "C1") (pin "2") (pinfunction "2_2") (pintype "passive"))
      (node (ref "C2") (pin "1") (pinfunction "1_1") (pintype "passive"))
      (node (ref "C3") (pin "2") (pinfunction "2_2") (pintype "passive"))
      (node (ref "C4") (pin "2") (pinfunction "2_2") (pintype "passive"))
      (node (ref "C5") (pin "2") (pinfunction "2_2") (pintype "passive"))
      (node (ref "P1") (pin "2") (pinfunction "2_2") (pintype "passive"))
      (node (ref "P14") (pin "2") (pinfunction "2_2") (pintype "passive"))
      (node (ref "P2") (pin "2") (pinfunction "2_2") (pintype "passive"))
      (node (ref "P3") (pin "2") (pinfunction "2_2") (pintype "passive"))
      (node (ref "P4") (pin "2") (pinfunction "2_2") (pintype "passive"))
      (node (ref "P4") (pin "4") (pinfunction "4_4") (pintype "passive"))
      (node (ref "P5") (pin "1") (pinfunction "1_1") (pintype "passive"))
      (node (ref "P5") (pin "2") (pinfunction "2_2") (pintype "passive"))
      (node (ref "P5") (pin "23") (pinfunction "23_23") (pintype "passive"))
      (node (ref "P5") (pin "24") (pinfunction "24_24") (pintype "passive"))
      (node (ref "P6") (pin "2") (pinfunction "2_2") (pintype "passive"))
      (node (ref "P8") (pin "2") (pinfunction "2_2") (pintype "passive"))
      (node (ref "Q1") (pin "3") (pinfunction "S_3") (pintype "passive"))
      (node (ref "Q2") (pin "3") (pinfunction "S_3") (pintype "passive"))
      (node (ref "Q3") (pin "3") (pinfunction "S_3") (pintype "passive"))
      (node (ref "Q4") (pin "3") (pinfunction "S_3") (pintype "passive"))
      (node (ref "Q5") (pin "3") (pinfunction "S_3") (pintype "passive"))
      (node (ref "Q6") (pin "3") (pinfunction "S_3") (pintype "passive"))
      (node (ref "U1") (pin "2") (pinfunction "GND_2") (pintype "passive"))
      (node (ref "U2") (pin "12") (pinfunction "GND_12") (pintype "power_in"))
      (node (ref "U2") (pin "27") (pinfunction "VSS_27") (pintype "power_in"))
      (node (ref "U3") (pin "2") (pinfunction "DGND_2") (pintype "power_in"))
      (node (ref "U3") (pin "4") (pinfunction "AGND_4") (pintype "power_in"))
      (node (ref "U3") (pin "8") (pinfunction "AGND_8") (pintype "power_in"))
    )
    (net (code "49") (name "Net-(Q1-G)") (class "Default")
      (node (ref "Q1") (pin "1") (pinfunction "G_1") (pintype "passive"))
      (node (ref "R4") (pin "2") (pinfunction "2_2") (pintype "passive"))
    )
    (net (code "50") (name "Net-(Q2-G)") (class "Default")
      (node (ref "Q2") (pin "1") (pinfunction "G_1") (pintype "passive"))
      (node (ref "R5") (pin "2") (pinfunction "2_2") (pintype "passive"))
    )
    (net (code "51") (name "Net-(Q3-G)") (class "Default")
      (node (ref "Q3") (pin "1") (pinfunction "G_1") (pintype "passive"))
      (node (ref "R9") (pin "2") (pinfunction "2_2") (pintype "passive"))
    )
    (net (code "52") (name "Net-(Q4-G)") (class "Default")
      (node (ref "Q4") (pin "1") (pinfunction "G_1") (pintype "passive"))
      (node (ref "R10") (pin "2") (pinfunction "2_2") (pintype "passive"))
    )
    (net (code "53") (name "Net-(Q5-G)") (class "Default")
      (node (ref "Q5") (pin "1") (pinfunction "G_1") (pintype "passive"))
      (node (ref "R16") (pin "2") (pinfunction "2_2") (pintype "passive"))
    )
    (net (code "54") (name "Net-(Q6-G)") (class "Default")
      (node (ref "Q6") (pin "1") (pinfunction "G_1") (pintype "passive"))
      (node (ref "R17") (pin "2") (pinfunction "2_2") (pintype "passive"))
    )
    (net (code "55") (name "Net-(U1-Filter)") (class "Default")
      (node (ref "C1") (pin "1") (pinfunction "1_1") (pintype "passive"))
      (node (ref "U1") (pin "1") (pinfunction "Filter_1") (pintype "passive"))
    )
    (net (code "56") (name "unconnected-(P5-Pad4)") (class "Default")
      (node (ref "P5") (pin "4") (pinfunction "4_4") (pintype "passive+no_connect"))
    )
    (net (code "57") (name "unconnected-(P5-Pad5)") (class "Default")
      (node (ref "P5") (pin "5") (pinfunction "5_5") (pintype "passive+no_connect"))
    )
    (net (code "58") (name "unconnected-(U2-NC-Pad2)") (class "Default")
      (node (ref "U2") (pin "2") (pinfunction "NC_2") (pintype "passive"))
    )
    (net (code "59") (name "unconnected-(U2-NC-Pad3)") (class "Default")
      (node (ref "U2") (pin "3") (pinfunction "NC_3") (pintype "passive"))
    )
    (net (code "60") (name "unconnected-(U2-NC-Pad13)") (class "Default")
      (node (ref "U2") (pin "13") (pinfunction "NC_13") (pintype "passive"))
    )
    (net (code "61") (name "unconnected-(U2-S11-Pad9)") (class "Default")
      (node (ref "U2") (pin "9") (pinfunction "S11_9") (pintype "passive"))
    )
    (net (code "62") (name "unconnected-(U2-S12-Pad8)") (class "Default")
      (node (ref "U2") (pin "8") (pinfunction "S12_8") (pintype "passive"))
    )
    (net (code "63") (name "unconnected-(U2-S13-Pad7)") (class "Default")
      (node (ref "U2") (pin "7") (pinfunction "S13_7") (pintype "passive"))
    )
    (net (code "64") (name "unconnected-(U2-S14-Pad6)") (class "Default")
      (node (ref "U2") (pin "6") (pinfunction "S14_6") (pintype "passive"))
    )
    (net (code "65") (name "unconnected-(U2-S15-Pad5)") (class "Default")
      (node (ref "U2") (pin "5") (pinfunction "S15_5") (pintype "passive"))
    )
    (net (code "66") (name "unconnected-(U2-S16-Pad4)") (class "Default")
      (node (ref "U2") (pin "4") (pinfunction "S16_4") (pintype "passive"))
    )
  )
)
